# ZH.net
KiCad netlist of a schematic drawn in Altium Designer
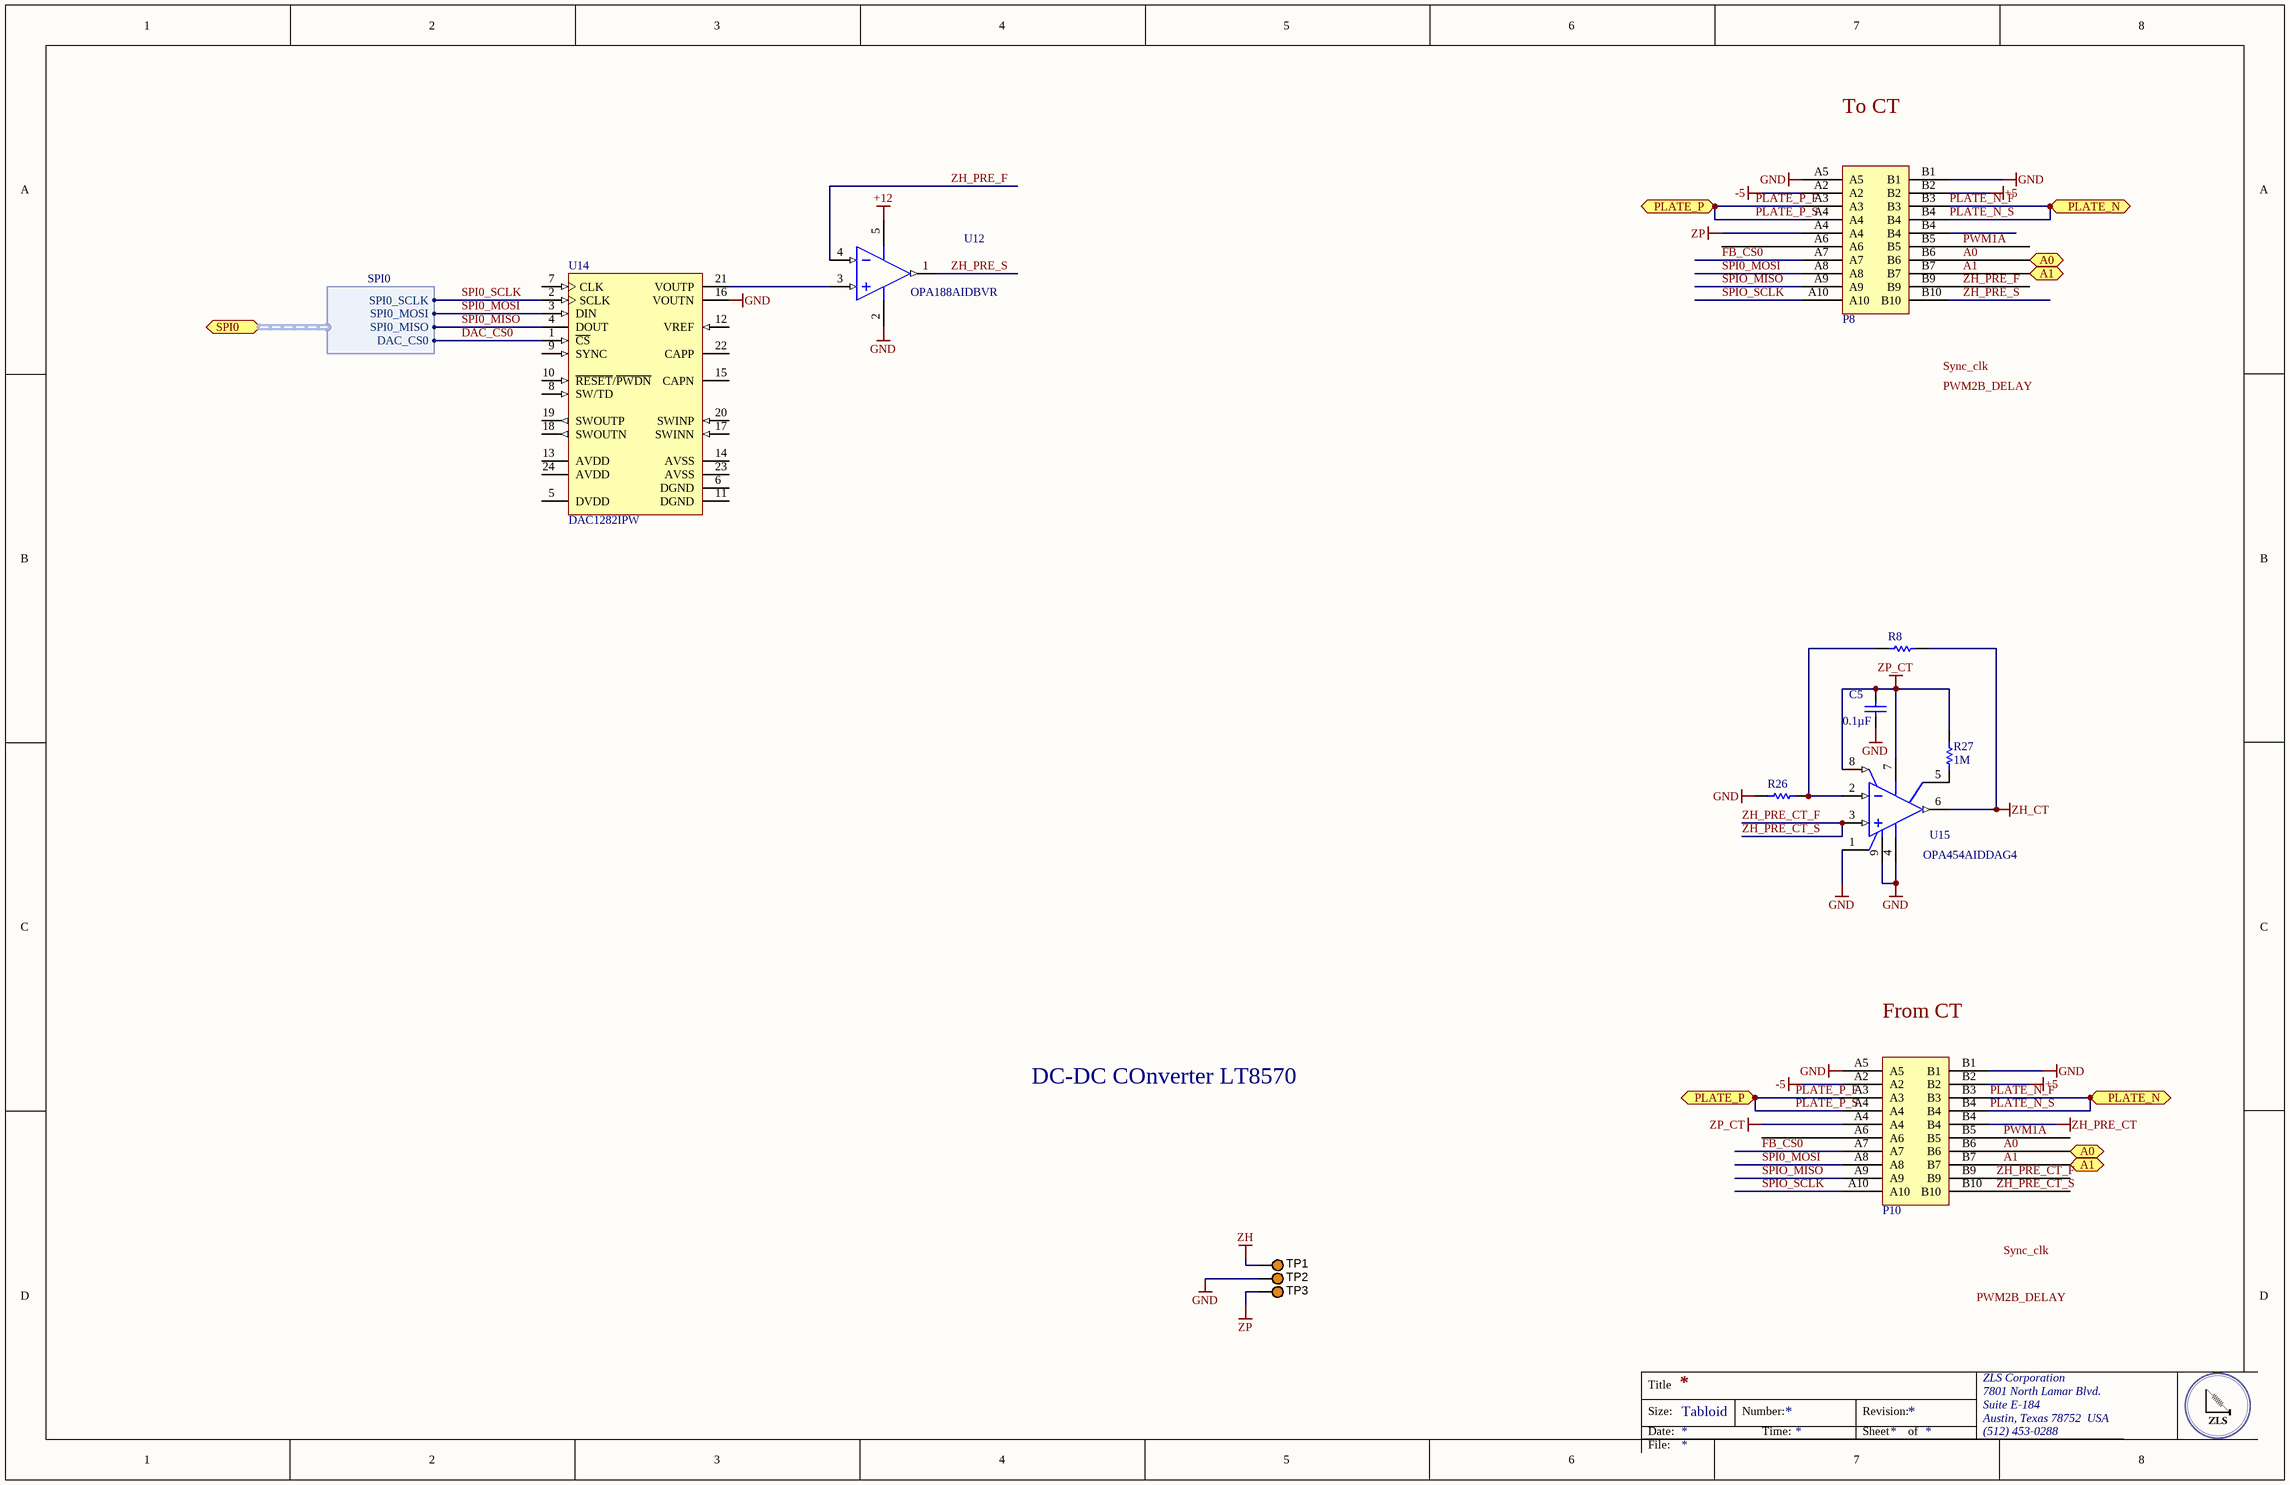
[diagram p0: ZH.SchDoc]

(export (version "E")
  (design (tool "Eeschema 10.0.6"))
  (components
    (comp (ref "C5")
      (value "CAP CER 0.1UF 25V X7R 0805")
      (footprint "CAPC0805(2012)145_N")
      (fields
        (field (name "MANUFACTURER") "Murata Electronics North America")
        (field (name "MANUFACTURER PART NUMBER") "GRM21BR71E104KA01L")
        (field (name "CAPACITANCE") "0.1µF")
        (field (name "TOLERANCE") "±10%")
      )
      (libsource (lib "Altium Content Vault") (part "CMP-1036-04795-1"))
    )
    (comp (ref "P8")
      (value "MEC6-110-0-PCB")
      (footprint "MEC6-110-02-L-DV")
      (libsource (lib "ZLS_Schematic_lib") (part "MEC6-110-0-PCB"))
    )
    (comp (ref "P10")
      (value "MEC6-110-0-PCB")
      (footprint "MEC6-110-02-L-DV")
      (libsource (lib "ZLS_Schematic_lib") (part "MEC6-110-0-PCB"))
    )
    (comp (ref "R8")
      (value "~")
      (footprint "RESC0402(1005)_M")
      (libsource (lib "Altium Content Vault") (part "CMP-1011-00463-1"))
    )
    (comp (ref "R26")
      (value "~")
      (footprint "RESC0402(1005)_M")
      (libsource (lib "Altium Content Vault") (part "CMP-1011-00463-1"))
    )
    (comp (ref "R27")
      (value "1M")
      (footprint "RESC0402(1005)_M")
      (libsource (lib "Altium Content Vault") (part "CMP-1011-00463-1"))
    )
    (comp (ref "TP1")
      (value "5003")
      (footprint "KSTN-5003")
      (description "Test Point, Orange, 1-Pin THD, RoHS")
      (libsource (lib "Altium Content Vault") (part "CMP-1672-00009-1"))
    )
    (comp (ref "TP2")
      (value "5003")
      (footprint "KSTN-5003")
      (description "Test Point, Orange, 1-Pin THD, RoHS")
      (libsource (lib "Altium Content Vault") (part "CMP-1672-00009-1"))
    )
    (comp (ref "TP3")
      (value "5003")
      (footprint "KSTN-5003")
      (description "Test Point, Orange, 1-Pin THD, RoHS")
      (libsource (lib "Altium Content Vault") (part "CMP-1672-00009-1"))
    )
    (comp (ref "U12")
      (value "OPA188AIDBVR")
      (footprint "DBV0005A_M")
      (fields (field (name "MANUFACTURER") "Texas Instruments"))
      (libsource (lib "Altium Content Vault") (part "CMP-0809-00005-2"))
    )
    (comp (ref "U14")
      (value "DAC1282IPW")
      (footprint "TI-PW24_M")
      (fields (field (name "MANUFACTURER") "Texas Instruments"))
      (libsource (lib "Altium Content Vault") (part "TI-DAC1282PW24"))
    )
    (comp (ref "U15")
      (value "OPA454AIDDAG4")
      (footprint "TI-DDA8-2745X2245TP_N")
      (fields (field (name "MANUFACTURER") "Texas Instruments"))
      (libsource (lib "Altium Content Vault") (part "TI-OPA454-DDA8"))
    )
  )
  (nets
    (net (code "2") (name "+5") (class "Default")
      (node (ref "P10") (pin "B2") (pinfunction "B2_B2") (pintype "passive"))
      (node (ref "P8") (pin "B2") (pinfunction "B2_B2") (pintype "passive"))
    )
    (net (code "3") (name "+12") (class "Default")
      (node (ref "U12") (pin "5") (pinfunction "V+_5") (pintype "power_in"))
    )
    (net (code "4") (name "-5") (class "Default")
      (node (ref "P10") (pin "A2") (pinfunction "A2_A2") (pintype "passive"))
      (node (ref "P8") (pin "A2") (pinfunction "A2_A2") (pintype "passive"))
    )
    (net (code "5") (name "/A0") (class "Default")
      (node (ref "P10") (pin "B6") (pinfunction "B6_B6") (pintype "passive"))
      (node (ref "P8") (pin "B6") (pinfunction "B6_B6") (pintype "passive"))
    )
    (net (code "6") (name "/A1") (class "Default")
      (node (ref "P10") (pin "B7") (pinfunction "B7_B7") (pintype "passive"))
      (node (ref "P8") (pin "B7") (pinfunction "B7_B7") (pintype "passive"))
    )
    (net (code "7") (name "/DAC_CS0") (class "Default")
      (node (ref "U14") (pin "1") (pinfunction "~{CS}_1") (pintype "input"))
    )
    (net (code "8") (name "/FB_CS0") (class "Default")
      (node (ref "P10") (pin "A7") (pinfunction "A7_A7") (pintype "passive"))
      (node (ref "P8") (pin "A7") (pinfunction "A7_A7") (pintype "passive"))
    )
    (net (code "9") (name "/PLATE_N_F") (class "Default")
      (node (ref "P10") (pin "B3") (pinfunction "B3_B3") (pintype "passive"))
      (node (ref "P10") (pin "B4") (pinfunction "B4_B4") (pintype "passive"))
      (node (ref "P8") (pin "B3") (pinfunction "B3_B3") (pintype "passive"))
      (node (ref "P8") (pin "B4") (pinfunction "B4_B4") (pintype "passive"))
    )
    (net (code "10") (name "/PLATE_P_F") (class "Default")
      (node (ref "P10") (pin "A3") (pinfunction "A3_A3") (pintype "passive"))
      (node (ref "P10") (pin "A4") (pinfunction "A4_A4") (pintype "passive"))
      (node (ref "P8") (pin "A3") (pinfunction "A3_A3") (pintype "passive"))
      (node (ref "P8") (pin "A4") (pinfunction "A4_A4") (pintype "passive"))
    )
    (net (code "11") (name "/PWM1A") (class "Default")
      (node (ref "P10") (pin "B5") (pinfunction "B5_B5") (pintype "passive"))
      (node (ref "P8") (pin "B5") (pinfunction "B5_B5") (pintype "passive"))
    )
    (net (code "13") (name "/SPI0_MISO") (class "Default")
      (node (ref "U14") (pin "4") (pinfunction "DOUT_4") (pintype "tri_state"))
    )
    (net (code "14") (name "/SPI0_MOSI") (class "Default")
      (node (ref "P10") (pin "A8") (pinfunction "A8_A8") (pintype "passive"))
      (node (ref "P8") (pin "A8") (pinfunction "A8_A8") (pintype "passive"))
      (node (ref "U14") (pin "3") (pinfunction "DIN_3") (pintype "input"))
    )
    (net (code "15") (name "/SPI0_SCLK") (class "Default")
      (node (ref "U14") (pin "2") (pinfunction "SCLK_2") (pintype "input"))
    )
    (net (code "16") (name "/SPIO_MISO") (class "Default")
      (node (ref "P10") (pin "A9") (pinfunction "A9_A9") (pintype "passive"))
      (node (ref "P8") (pin "A9") (pinfunction "A9_A9") (pintype "passive"))
    )
    (net (code "17") (name "/SPIO_SCLK") (class "Default")
      (node (ref "P10") (pin "A10") (pinfunction "A10_A10") (pintype "passive"))
      (node (ref "P8") (pin "A10") (pinfunction "A10_A10") (pintype "passive"))
    )
    (net (code "19") (name "/ZH_PRE_CT_F") (class "Default")
      (node (ref "P10") (pin "B10") (pinfunction "B10_B10") (pintype "passive"))
      (node (ref "P10") (pin "B9") (pinfunction "B9_B9") (pintype "passive"))
      (node (ref "U15") (pin "3") (pinfunction "IN+_3") (pintype "input"))
    )
    (net (code "20") (name "/ZH_PRE_F") (class "Default")
      (node (ref "P8") (pin "B9") (pinfunction "B9_B9") (pintype "passive"))
      (node (ref "U12") (pin "4") (pinfunction "IN-_4") (pintype "input"))
    )
    (net (code "21") (name "/ZH_PRE_S") (class "Default")
      (node (ref "P8") (pin "B10") (pinfunction "B10_B10") (pintype "passive"))
      (node (ref "U12") (pin "1") (pinfunction "OUT_1") (pintype "output"))
    )
    (net (code "23") (name "GND") (class "Default")
      (node (ref "C5") (pin "2") (pinfunction "2_2") (pintype "passive"))
      (node (ref "P10") (pin "A5") (pinfunction "A5_A5") (pintype "passive"))
      (node (ref "P10") (pin "B1") (pinfunction "B1_B1") (pintype "passive"))
      (node (ref "P8") (pin "A5") (pinfunction "A5_A5") (pintype "passive"))
      (node (ref "P8") (pin "B1") (pinfunction "B1_B1") (pintype "passive"))
      (node (ref "R26") (pin "2") (pinfunction "2_2") (pintype "passive"))
      (node (ref "TP2") (pin "1") (pinfunction "1_1") (pintype "passive"))
      (node (ref "U12") (pin "2") (pinfunction "V-_2") (pintype "power_in"))
      (node (ref "U14") (pin "16") (pinfunction "VOUTN_16") (pintype "tri_state"))
      (node (ref "U15") (pin "1") (pinfunction "E/D_COM_1") (pintype "power_in"))
      (node (ref "U15") (pin "4") (pinfunction "V-_4") (pintype "power_in"))
      (node (ref "U15") (pin "9") (pinfunction "EP_9") (pintype "power_in"))
    )
    (net (code "24") (name "Net-(U12-IN+)") (class "Default")
      (node (ref "U12") (pin "3") (pinfunction "IN+_3") (pintype "input"))
      (node (ref "U14") (pin "21") (pinfunction "VOUTP_21") (pintype "tri_state"))
    )
    (net (code "25") (name "Net-(U15-IN-)") (class "Default")
      (node (ref "R26") (pin "1") (pinfunction "1_1") (pintype "passive"))
      (node (ref "R8") (pin "2") (pinfunction "2_2") (pintype "passive"))
      (node (ref "U15") (pin "2") (pinfunction "IN-_2") (pintype "input"))
    )
    (net (code "26") (name "Net-(U15-STATUS_FLAG)") (class "Default")
      (node (ref "R27") (pin "1") (pinfunction "1_1") (pintype "passive"))
      (node (ref "U15") (pin "5") (pinfunction "STATUS_FLAG_5") (pintype "open_collector"))
    )
    (net (code "27") (name "ZH") (class "Default")
      (node (ref "TP1") (pin "1") (pinfunction "1_1") (pintype "passive"))
    )
    (net (code "28") (name "ZH_CT") (class "Default")
      (node (ref "R8") (pin "1") (pinfunction "1_1") (pintype "passive"))
      (node (ref "U15") (pin "6") (pinfunction "OUT_6") (pintype "output"))
    )
    (net (code "29") (name "ZH_PRE_CT") (class "Default")
      (node (ref "P10") (pin "B4") (pinfunction "B4_B4") (pintype "passive"))
    )
    (net (code "30") (name "ZP") (class "Default")
      (node (ref "P8") (pin "A4") (pinfunction "A4_A4") (pintype "passive"))
      (node (ref "TP3") (pin "1") (pinfunction "1_1") (pintype "passive"))
    )
    (net (code "31") (name "ZP_CT") (class "Default")
      (node (ref "C5") (pin "1") (pinfunction "1_1") (pintype "passive"))
      (node (ref "P10") (pin "A4") (pinfunction "A4_A4") (pintype "passive"))
      (node (ref "R27") (pin "2") (pinfunction "2_2") (pintype "passive"))
      (node (ref "U15") (pin "7") (pinfunction "V+_7") (pintype "power_in"))
      (node (ref "U15") (pin "8") (pinfunction "E/D_8") (pintype "input"))
    )
    (net (code "32") (name "unconnected-(P8-PadA6)") (class "Default")
      (node (ref "P8") (pin "A6") (pinfunction "A6_A6") (pintype "passive"))
    )
    (net (code "33") (name "unconnected-(P8-PadB4)") (class "Default")
      (node (ref "P8") (pin "B4") (pinfunction "B4_B4") (pintype "passive"))
    )
    (net (code "34") (name "unconnected-(P10-PadA6)") (class "Default")
      (node (ref "P10") (pin "A6") (pinfunction "A6_A6") (pintype "passive"))
    )
    (net (code "35") (name "unconnected-(U14-AVDD-Pad13)") (class "Default")
      (node (ref "U14") (pin "13") (pinfunction "AVDD_13") (pintype "power_in"))
    )
    (net (code "36") (name "unconnected-(U14-AVDD-Pad24)") (class "Default")
      (node (ref "U14") (pin "24") (pinfunction "AVDD_24") (pintype "power_in"))
    )
    (net (code "37") (name "unconnected-(U14-AVSS-Pad14)") (class "Default")
      (node (ref "U14") (pin "14") (pinfunction "AVSS_14") (pintype "power_in"))
    )
    (net (code "38") (name "unconnected-(U14-AVSS-Pad23)") (class "Default")
      (node (ref "U14") (pin "23") (pinfunction "AVSS_23") (pintype "power_in"))
    )
    (net (code "39") (name "unconnected-(U14-CAPN-Pad15)") (class "Default")
      (node (ref "U14") (pin "15") (pinfunction "CAPN_15") (pintype "passive"))
    )
    (net (code "40") (name "unconnected-(U14-CAPP-Pad22)") (class "Default")
      (node (ref "U14") (pin "22") (pinfunction "CAPP_22") (pintype "passive"))
    )
    (net (code "41") (name "unconnected-(U14-CLK-Pad7)") (class "Default")
      (node (ref "U14") (pin "7") (pinfunction "CLK_7") (pintype "input"))
    )
    (net (code "42") (name "unconnected-(U14-DGND-Pad6)") (class "Default")
      (node (ref "U14") (pin "6") (pinfunction "DGND_6") (pintype "power_in"))
    )
    (net (code "43") (name "unconnected-(U14-DGND-Pad11)") (class "Default")
      (node (ref "U14") (pin "11") (pinfunction "DGND_11") (pintype "power_in"))
    )
    (net (code "44") (name "unconnected-(U14-DVDD-Pad5)") (class "Default")
      (node (ref "U14") (pin "5") (pinfunction "DVDD_5") (pintype "power_in"))
    )
    (net (code "45") (name "unconnected-(U14-SWINN-Pad17)") (class "Default")
      (node (ref "U14") (pin "17") (pinfunction "SWINN_17") (pintype "input"))
    )
    (net (code "46") (name "unconnected-(U14-SWINP-Pad20)") (class "Default")
      (node (ref "U14") (pin "20") (pinfunction "SWINP_20") (pintype "input"))
    )
    (net (code "47") (name "unconnected-(U14-SWOUTN-Pad18)") (class "Default")
      (node (ref "U14") (pin "18") (pinfunction "SWOUTN_18") (pintype "output"))
    )
    (net (code "48") (name "unconnected-(U14-SWOUTP-Pad19)") (class "Default")
      (node (ref "U14") (pin "19") (pinfunction "SWOUTP_19") (pintype "output"))
    )
    (net (code "49") (name "unconnected-(U14-SW{slash}TD-Pad8)") (class "Default")
      (node (ref "U14") (pin "8") (pinfunction "SW/TD_8") (pintype "input"))
    )
    (net (code "50") (name "unconnected-(U14-SYNC-Pad9)") (class "Default")
      (node (ref "U14") (pin "9") (pinfunction "SYNC_9") (pintype "input"))
    )
    (net (code "51") (name "unconnected-(U14-VREF-Pad12)") (class "Default")
      (node (ref "U14") (pin "12") (pinfunction "VREF_12") (pintype "input"))
    )
    (net (code "52") (name "unconnected-(U14-~{RESET}{slash}~{PWDN}-Pad10)") (class "Default")
      (node (ref "U14") (pin "10") (pinfunction "~{RESET}/~{PWDN}_10") (pintype "input"))
    )
  )
)
